# 04_LMS7002M_Misc.net
KiCad netlist of a schematic drawn in Altium Designer
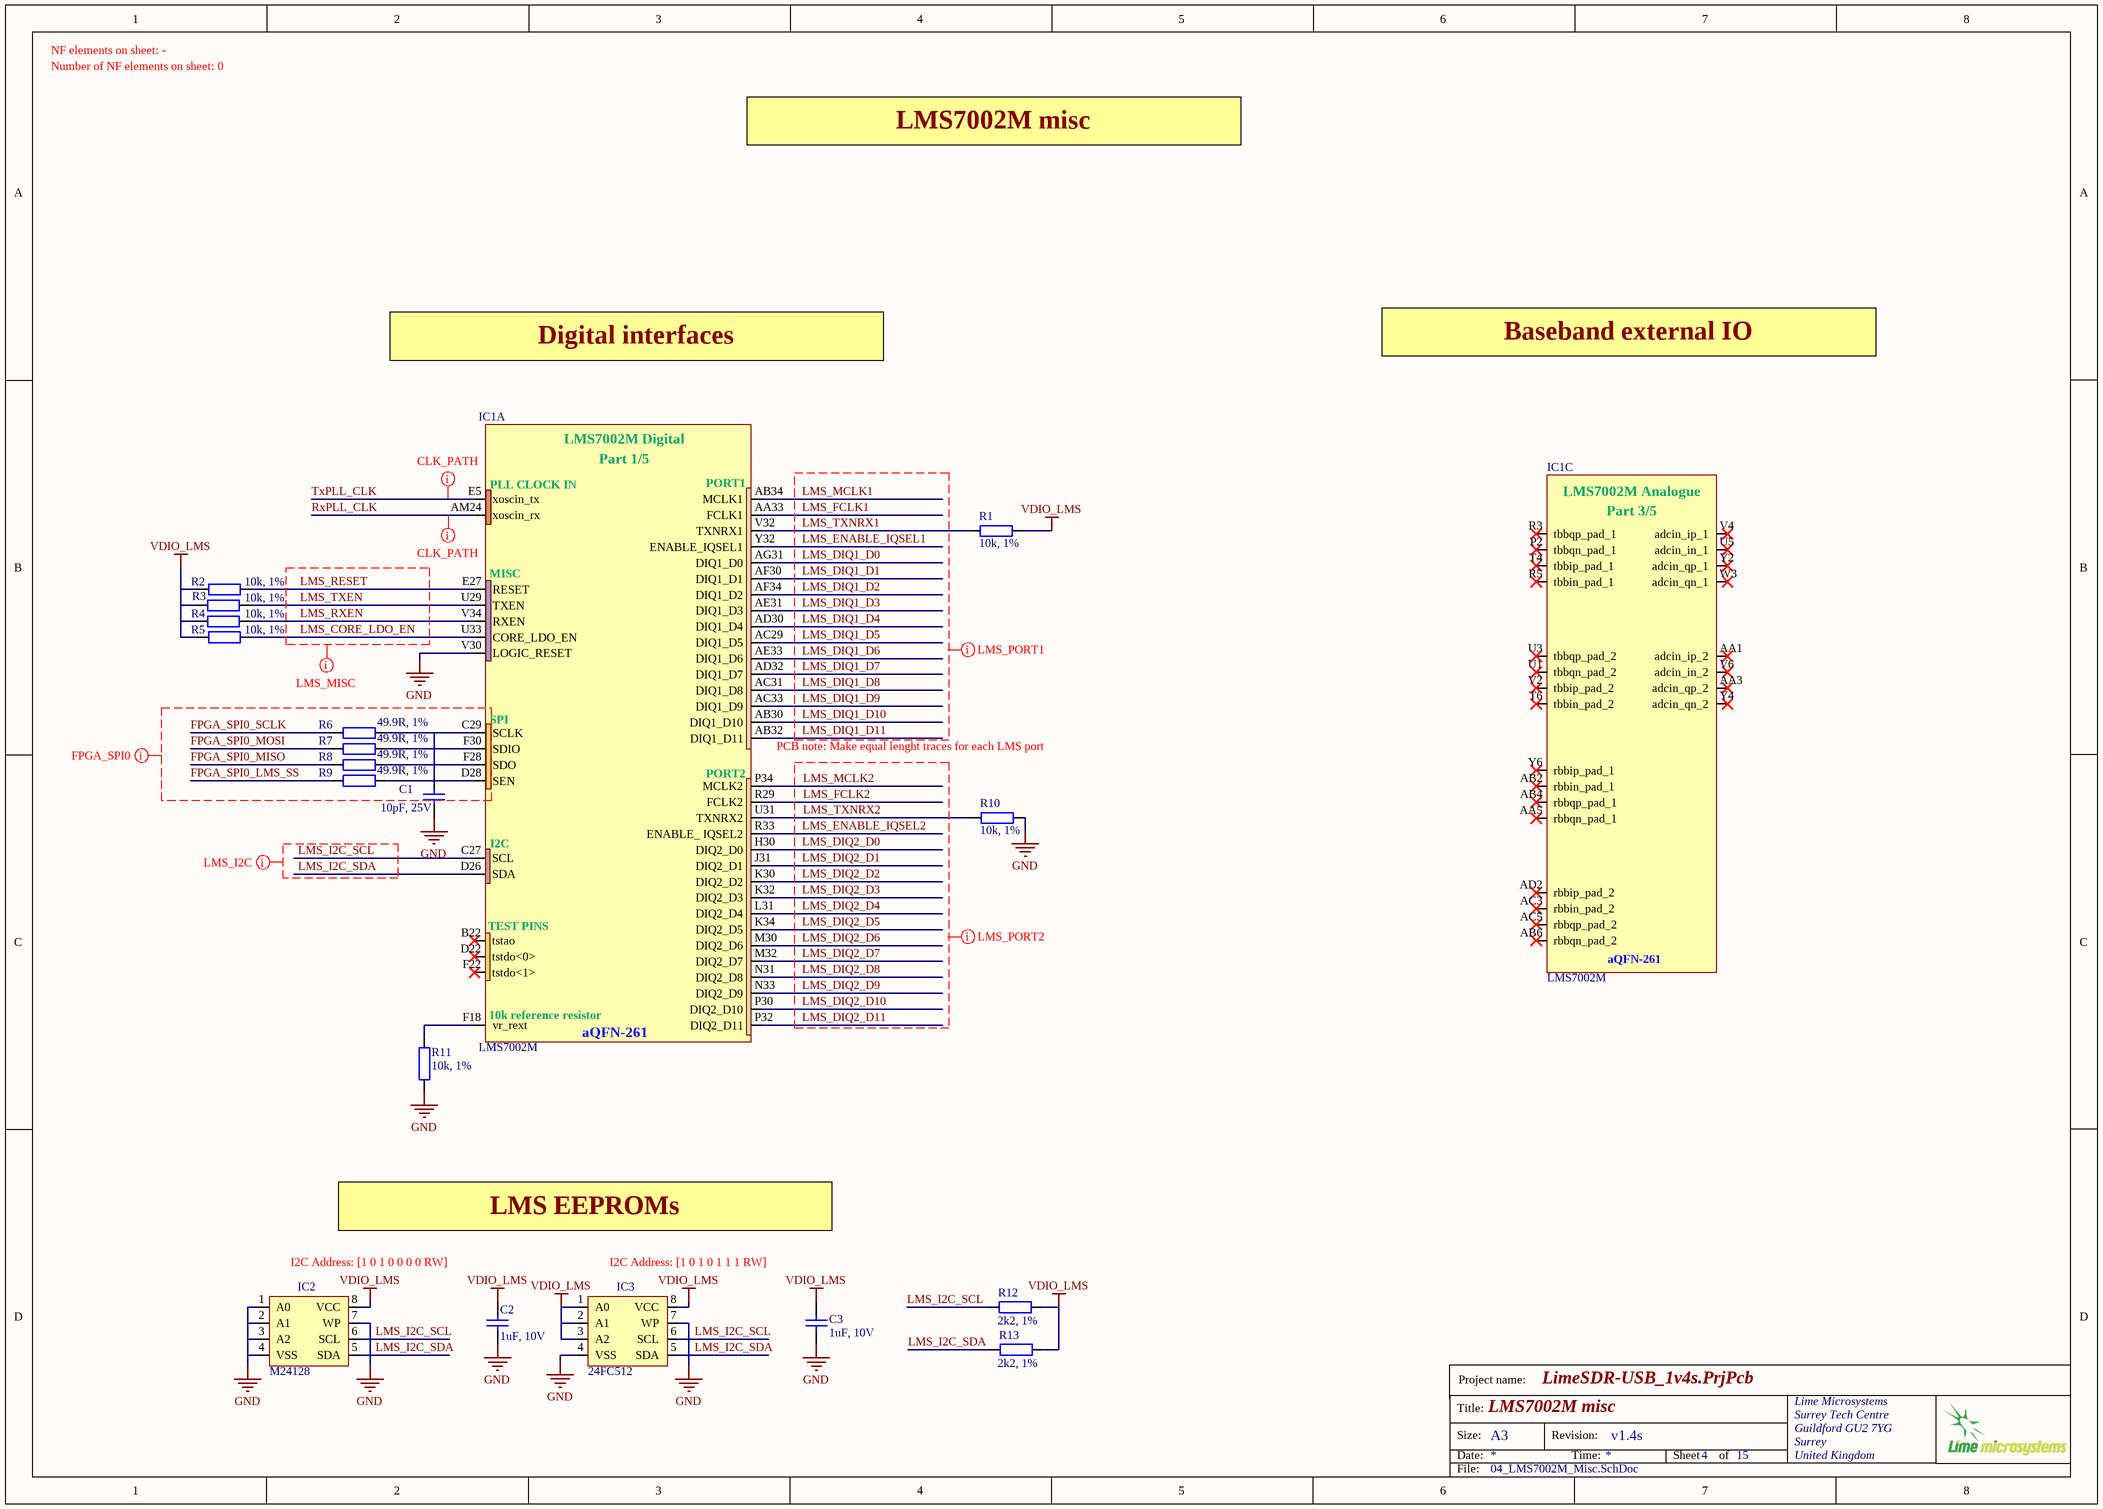
[diagram p0: 04_LMS7002M_Misc.SchDoc]

(export (version "E")
  (design (tool "Eeschema 10.0.6"))
  (components
    (comp (ref "C1")
      (value "10pF, 25V")
      (footprint "CAP0402")
      (fields (field (name "MANUFACTURER") "AVX"))
      (libsource (lib "LimeMicroAltiumLib_schLib") (part "Cap_0402"))
    )
    (comp (ref "C2")
      (value "1uF, 10V")
      (footprint "CAP0402")
      (fields (field (name "MANUFACTURER") "TDK"))
      (libsource (lib "LimeMicroAltiumLib_schLib") (part "Cap_0402"))
    )
    (comp (ref "C3")
      (value "1uF, 10V")
      (footprint "CAP0402")
      (fields (field (name "MANUFACTURER") "TDK"))
      (libsource (lib "LimeMicroAltiumLib_schLib") (part "Cap_0402"))
    )
    (comp (ref "IC1")
      (value "LMS7002M")
      (footprint "LMS7002M_v3")
      (fields (field (name "MANUFACTURER") "Lime Microsystems"))
      (libsource (lib "LimeMicroAltiumLib_schLib") (part "LMS7002M"))
    )
    (comp (ref "IC2")
      (value "M24128")
      (footprint "24FC512")
      (fields (field (name "MANUFACTURER") "STMicroelectronics"))
      (libsource (lib "LimeMicroAltiumLib_schLib") (part "24FC64F"))
    )
    (comp (ref "IC3")
      (value "24FC512")
      (footprint "24FC512")
      (fields (field (name "MANUFACTURER") "Microchip Technology"))
      (libsource (lib "LimeMicroAltiumLib_schLib") (part "24FC512"))
    )
    (comp (ref "R1")
      (value "10k, 1%")
      (footprint "RES0402")
      (fields (field (name "MANUFACTURER") "Yageo") (field (name "TOLERANCE") "±1%"))
      (libsource (lib "LimeMicroAltiumLib_schLib") (part "Res_0402"))
    )
    (comp (ref "R2")
      (value "10k, 1%")
      (footprint "RES0402")
      (fields (field (name "MANUFACTURER") "Yageo") (field (name "TOLERANCE") "±1%"))
      (libsource (lib "LimeMicroAltiumLib_schLib") (part "Res_0402"))
    )
    (comp (ref "R3")
      (value "10k, 1%")
      (footprint "RES0402")
      (fields (field (name "MANUFACTURER") "Yageo") (field (name "TOLERANCE") "±1%"))
      (libsource (lib "LimeMicroAltiumLib_schLib") (part "Res_0402"))
    )
    (comp (ref "R4")
      (value "10k, 1%")
      (footprint "RES0402")
      (fields (field (name "MANUFACTURER") "Yageo") (field (name "TOLERANCE") "±1%"))
      (libsource (lib "LimeMicroAltiumLib_schLib") (part "Res_0402"))
    )
    (comp (ref "R5")
      (value "10k, 1%")
      (footprint "RES0402")
      (fields (field (name "MANUFACTURER") "Yageo") (field (name "TOLERANCE") "±1%"))
      (libsource (lib "LimeMicroAltiumLib_schLib") (part "Res_0402"))
    )
    (comp (ref "R6")
      (value "49.9R, 1%")
      (footprint "RES0402")
      (fields
        (field (name "TOLERANCE") "±1%")
        (field (name "MANUFACTURER") "Samsung Electro-Mechanics America, Inc.")
        (field (name "MANUFACTURER PART NUMBER") "RC1005F49R9CS")
      )
      (libsource (lib "LimeMicroAltiumLib_schLib") (part "Res_0402"))
    )
    (comp (ref "R7")
      (value "49.9R, 1%")
      (footprint "RES0402")
      (fields
        (field (name "TOLERANCE") "±1%")
        (field (name "MANUFACTURER") "Samsung Electro-Mechanics America, Inc.")
        (field (name "MANUFACTURER PART NUMBER") "RC1005F49R9CS")
      )
      (libsource (lib "LimeMicroAltiumLib_schLib") (part "Res_0402"))
    )
    (comp (ref "R8")
      (value "49.9R, 1%")
      (footprint "RES0402")
      (fields
        (field (name "TOLERANCE") "±1%")
        (field (name "MANUFACTURER") "Samsung Electro-Mechanics America, Inc.")
        (field (name "MANUFACTURER PART NUMBER") "RC1005F49R9CS")
      )
      (libsource (lib "LimeMicroAltiumLib_schLib") (part "Res_0402"))
    )
    (comp (ref "R9")
      (value "49.9R, 1%")
      (footprint "RES0402")
      (fields
        (field (name "TOLERANCE") "±1%")
        (field (name "MANUFACTURER") "Samsung Electro-Mechanics America, Inc.")
        (field (name "MANUFACTURER PART NUMBER") "RC1005F49R9CS")
      )
      (libsource (lib "LimeMicroAltiumLib_schLib") (part "Res_0402"))
    )
    (comp (ref "R10")
      (value "10k, 1%")
      (footprint "RES0402")
      (fields (field (name "MANUFACTURER") "Yageo") (field (name "TOLERANCE") "±1%"))
      (libsource (lib "LimeMicroAltiumLib_schLib") (part "Res_0402"))
    )
    (comp (ref "R11")
      (value "10k, 1%")
      (footprint "RES0402")
      (fields (field (name "MANUFACTURER") "Yageo") (field (name "TOLERANCE") "±1%"))
      (libsource (lib "LimeMicroAltiumLib_schLib") (part "Res_0402"))
    )
    (comp (ref "R12")
      (value "2k2, 1%")
      (footprint "RES0402")
      (fields (field (name "MANUFACTURER") "Stackpole Electronics Inc") (field (name "TOLERANCE") "±1%"))
      (libsource (lib "LimeMicroAltiumLib_schLib") (part "Res_0402"))
    )
    (comp (ref "R13")
      (value "2k2, 1%")
      (footprint "RES0402")
      (fields (field (name "MANUFACTURER") "Stackpole Electronics Inc") (field (name "TOLERANCE") "±1%"))
      (libsource (lib "LimeMicroAltiumLib_schLib") (part "Res_0402"))
    )
  )
  (nets
    (net (code "1") (name "/FPGA_SPI0_LMS_SS") (class "Default")
      (node (ref "R9") (pin "2") (pinfunction "2_2") (pintype "passive"))
    )
    (net (code "2") (name "/FPGA_SPI0_MISO") (class "Default")
      (node (ref "R8") (pin "2") (pinfunction "2_2") (pintype "passive"))
    )
    (net (code "3") (name "/FPGA_SPI0_MOSI") (class "Default")
      (node (ref "R7") (pin "2") (pinfunction "2_2") (pintype "passive"))
    )
    (net (code "4") (name "/FPGA_SPI0_SCLK") (class "Default")
      (node (ref "R6") (pin "2") (pinfunction "2_2") (pintype "passive"))
    )
    (net (code "5") (name "/LMS_CORE_LDO_EN") (class "Default")
      (node (ref "IC1") (pin "U33") (pinfunction "CORE_LDO_EN_U33") (pintype "passive"))
      (node (ref "R5") (pin "1") (pinfunction "1_1") (pintype "passive"))
    )
    (net (code "6") (name "/LMS_DIQ1_D0") (class "Default")
      (node (ref "IC1") (pin "AG31") (pinfunction "DIQ1_D0_AG31") (pintype "passive"))
    )
    (net (code "7") (name "/LMS_DIQ1_D1") (class "Default")
      (node (ref "IC1") (pin "AF30") (pinfunction "DIQ1_D1_AF30") (pintype "passive"))
    )
    (net (code "8") (name "/LMS_DIQ1_D2") (class "Default")
      (node (ref "IC1") (pin "AF34") (pinfunction "DIQ1_D2_AF34") (pintype "passive"))
    )
    (net (code "9") (name "/LMS_DIQ1_D3") (class "Default")
      (node (ref "IC1") (pin "AE31") (pinfunction "DIQ1_D3_AE31") (pintype "passive"))
    )
    (net (code "10") (name "/LMS_DIQ1_D4") (class "Default")
      (node (ref "IC1") (pin "AD30") (pinfunction "DIQ1_D4_AD30") (pintype "passive"))
    )
    (net (code "11") (name "/LMS_DIQ1_D5") (class "Default")
      (node (ref "IC1") (pin "AC29") (pinfunction "DIQ1_D5_AC29") (pintype "passive"))
    )
    (net (code "12") (name "/LMS_DIQ1_D6") (class "Default")
      (node (ref "IC1") (pin "AE33") (pinfunction "DIQ1_D6_AE33") (pintype "passive"))
    )
    (net (code "13") (name "/LMS_DIQ1_D7") (class "Default")
      (node (ref "IC1") (pin "AD32") (pinfunction "DIQ1_D7_AD32") (pintype "passive"))
    )
    (net (code "14") (name "/LMS_DIQ1_D8") (class "Default")
      (node (ref "IC1") (pin "AC31") (pinfunction "DIQ1_D8_AC31") (pintype "passive"))
    )
    (net (code "15") (name "/LMS_DIQ1_D9") (class "Default")
      (node (ref "IC1") (pin "AC33") (pinfunction "DIQ1_D9_AC33") (pintype "passive"))
    )
    (net (code "16") (name "/LMS_DIQ1_D10") (class "Default")
      (node (ref "IC1") (pin "AB30") (pinfunction "DIQ1_D10_AB30") (pintype "passive"))
    )
    (net (code "17") (name "/LMS_DIQ1_D11") (class "Default")
      (node (ref "IC1") (pin "AB32") (pinfunction "DIQ1_D11_AB32") (pintype "passive"))
    )
    (net (code "18") (name "/LMS_DIQ2_D0") (class "Default")
      (node (ref "IC1") (pin "H30") (pinfunction "DIQ2_D0_H30") (pintype "passive"))
    )
    (net (code "19") (name "/LMS_DIQ2_D1") (class "Default")
      (node (ref "IC1") (pin "J31") (pinfunction "DIQ2_D1_J31") (pintype "passive"))
    )
    (net (code "20") (name "/LMS_DIQ2_D2") (class "Default")
      (node (ref "IC1") (pin "K30") (pinfunction "DIQ2_D2_K30") (pintype "passive"))
    )
    (net (code "21") (name "/LMS_DIQ2_D3") (class "Default")
      (node (ref "IC1") (pin "K32") (pinfunction "DIQ2_D3_K32") (pintype "passive"))
    )
    (net (code "22") (name "/LMS_DIQ2_D4") (class "Default")
      (node (ref "IC1") (pin "L31") (pinfunction "DIQ2_D4_L31") (pintype "passive"))
    )
    (net (code "23") (name "/LMS_DIQ2_D5") (class "Default")
      (node (ref "IC1") (pin "K34") (pinfunction "DIQ2_D5_K34") (pintype "passive"))
    )
    (net (code "24") (name "/LMS_DIQ2_D6") (class "Default")
      (node (ref "IC1") (pin "M30") (pinfunction "DIQ2_D6_M30") (pintype "passive"))
    )
    (net (code "25") (name "/LMS_DIQ2_D7") (class "Default")
      (node (ref "IC1") (pin "M32") (pinfunction "DIQ2_D7_M32") (pintype "passive"))
    )
    (net (code "26") (name "/LMS_DIQ2_D8") (class "Default")
      (node (ref "IC1") (pin "N31") (pinfunction "DIQ2_D8_N31") (pintype "passive"))
    )
    (net (code "27") (name "/LMS_DIQ2_D9") (class "Default")
      (node (ref "IC1") (pin "N33") (pinfunction "DIQ2_D9_N33") (pintype "passive"))
    )
    (net (code "28") (name "/LMS_DIQ2_D10") (class "Default")
      (node (ref "IC1") (pin "P30") (pinfunction "DIQ2_D10_P30") (pintype "passive"))
    )
    (net (code "29") (name "/LMS_DIQ2_D11") (class "Default")
      (node (ref "IC1") (pin "P32") (pinfunction "DIQ2_D11_P32") (pintype "passive"))
    )
    (net (code "30") (name "/LMS_ENABLE_IQSEL1") (class "Default")
      (node (ref "IC1") (pin "Y32") (pinfunction "ENABLE_IQSEL1_Y32") (pintype "passive"))
    )
    (net (code "31") (name "/LMS_ENABLE_IQSEL2") (class "Default")
      (node (ref "IC1") (pin "R33") (pinfunction "ENABLE__IQSEL2_R33") (pintype "passive"))
    )
    (net (code "32") (name "/LMS_FCLK1") (class "Default")
      (node (ref "IC1") (pin "AA33") (pinfunction "FCLK1_AA33") (pintype "passive"))
    )
    (net (code "33") (name "/LMS_FCLK2") (class "Default")
      (node (ref "IC1") (pin "R29") (pinfunction "FCLK2_R29") (pintype "passive"))
    )
    (net (code "34") (name "/LMS_I2C_SCL") (class "Default")
      (node (ref "IC1") (pin "C27") (pinfunction "SCL_C27") (pintype "passive"))
      (node (ref "IC2") (pin "6") (pinfunction "SCL_6") (pintype "passive"))
      (node (ref "IC3") (pin "6") (pinfunction "SCL_6") (pintype "passive"))
      (node (ref "R12") (pin "2") (pinfunction "2_2") (pintype "passive"))
    )
    (net (code "35") (name "/LMS_I2C_SDA") (class "Default")
      (node (ref "IC1") (pin "D26") (pinfunction "SDA_D26") (pintype "passive"))
      (node (ref "IC2") (pin "5") (pinfunction "SDA_5") (pintype "passive"))
      (node (ref "IC3") (pin "5") (pinfunction "SDA_5") (pintype "passive"))
      (node (ref "R13") (pin "2") (pinfunction "2_2") (pintype "passive"))
    )
    (net (code "36") (name "/LMS_MCLK1") (class "Default")
      (node (ref "IC1") (pin "AB34") (pinfunction "MCLK1_AB34") (pintype "passive"))
    )
    (net (code "37") (name "/LMS_MCLK2") (class "Default")
      (node (ref "IC1") (pin "P34") (pinfunction "MCLK2_P34") (pintype "passive"))
    )
    (net (code "38") (name "/LMS_RESET") (class "Default")
      (node (ref "IC1") (pin "E27") (pinfunction "RESET_E27") (pintype "passive"))
      (node (ref "R2") (pin "1") (pinfunction "1_1") (pintype "passive"))
    )
    (net (code "39") (name "/LMS_RXEN") (class "Default")
      (node (ref "IC1") (pin "V34") (pinfunction "RXEN_V34") (pintype "passive"))
      (node (ref "R4") (pin "2") (pinfunction "2_2") (pintype "passive"))
    )
    (net (code "40") (name "/LMS_TXEN") (class "Default")
      (node (ref "IC1") (pin "U29") (pinfunction "TXEN_U29") (pintype "passive"))
      (node (ref "R3") (pin "2") (pinfunction "2_2") (pintype "passive"))
    )
    (net (code "41") (name "/LMS_TXNRX1") (class "Default")
      (node (ref "IC1") (pin "V32") (pinfunction "TXNRX1_V32") (pintype "passive"))
      (node (ref "R1") (pin "1") (pinfunction "1_1") (pintype "passive"))
    )
    (net (code "42") (name "/LMS_TXNRX2") (class "Default")
      (node (ref "IC1") (pin "U31") (pinfunction "TXNRX2_U31") (pintype "passive"))
      (node (ref "R10") (pin "2") (pinfunction "2_2") (pintype "passive"))
    )
    (net (code "43") (name "/RxPLL_CLK") (class "Default")
      (node (ref "IC1") (pin "AM24") (pinfunction "xoscin_rx_AM24") (pintype "passive"))
    )
    (net (code "44") (name "/TxPLL_CLK") (class "Default")
      (node (ref "IC1") (pin "E5") (pinfunction "xoscin_tx_E5") (pintype "passive"))
    )
    (net (code "45") (name "GND") (class "Default")
      (node (ref "C1") (pin "2") (pinfunction "2_2") (pintype "passive"))
      (node (ref "C2") (pin "2") (pinfunction "2_2") (pintype "passive"))
      (node (ref "C3") (pin "1") (pinfunction "1_1") (pintype "passive"))
      (node (ref "IC1") (pin "V30") (pinfunction "LOGIC_RESET_V30") (pintype "passive"))
      (node (ref "IC2") (pin "1") (pinfunction "A0_1") (pintype "passive"))
      (node (ref "IC2") (pin "2") (pinfunction "A1_2") (pintype "passive"))
      (node (ref "IC2") (pin "3") (pinfunction "A2_3") (pintype "passive"))
      (node (ref "IC2") (pin "4") (pinfunction "VSS_4") (pintype "passive"))
      (node (ref "IC2") (pin "7") (pinfunction "WP_7") (pintype "passive"))
      (node (ref "IC3") (pin "4") (pinfunction "VSS_4") (pintype "passive"))
      (node (ref "IC3") (pin "7") (pinfunction "WP_7") (pintype "passive"))
      (node (ref "R10") (pin "1") (pinfunction "1_1") (pintype "passive"))
      (node (ref "R11") (pin "2") (pinfunction "2_2") (pintype "passive"))
    )
    (net (code "46") (name "Net-(IC1A-SCLK)") (class "Default")
      (node (ref "C1") (pin "1") (pinfunction "1_1") (pintype "passive"))
      (node (ref "IC1") (pin "C29") (pinfunction "SCLK_C29") (pintype "passive"))
      (node (ref "R6") (pin "1") (pinfunction "1_1") (pintype "passive"))
    )
    (net (code "47") (name "Net-(IC1A-SDIO)") (class "Default")
      (node (ref "IC1") (pin "F30") (pinfunction "SDIO_F30") (pintype "passive"))
      (node (ref "R7") (pin "1") (pinfunction "1_1") (pintype "passive"))
    )
    (net (code "48") (name "Net-(IC1A-SDO)") (class "Default")
      (node (ref "IC1") (pin "F28") (pinfunction "SDO_F28") (pintype "passive"))
      (node (ref "R8") (pin "1") (pinfunction "1_1") (pintype "passive"))
    )
    (net (code "49") (name "Net-(IC1A-SEN)") (class "Default")
      (node (ref "IC1") (pin "D28") (pinfunction "SEN_D28") (pintype "passive"))
      (node (ref "R9") (pin "1") (pinfunction "1_1") (pintype "passive"))
    )
    (net (code "50") (name "Net-(IC1A-vr_rext)") (class "Default")
      (node (ref "IC1") (pin "F18") (pinfunction "vr_rext_F18") (pintype "passive"))
      (node (ref "R11") (pin "1") (pinfunction "1_1") (pintype "passive"))
    )
    (net (code "51") (name "VDIO_LMS") (class "Default")
      (node (ref "C2") (pin "1") (pinfunction "1_1") (pintype "passive"))
      (node (ref "C3") (pin "2") (pinfunction "2_2") (pintype "passive"))
      (node (ref "IC2") (pin "8") (pinfunction "VCC_8") (pintype "passive"))
      (node (ref "IC3") (pin "1") (pinfunction "A0_1") (pintype "passive"))
      (node (ref "IC3") (pin "2") (pinfunction "A1_2") (pintype "passive"))
      (node (ref "IC3") (pin "3") (pinfunction "A2_3") (pintype "passive"))
      (node (ref "IC3") (pin "8") (pinfunction "VCC_8") (pintype "passive"))
      (node (ref "R1") (pin "2") (pinfunction "2_2") (pintype "passive"))
      (node (ref "R12") (pin "1") (pinfunction "1_1") (pintype "passive"))
      (node (ref "R13") (pin "1") (pinfunction "1_1") (pintype "passive"))
      (node (ref "R2") (pin "2") (pinfunction "2_2") (pintype "passive"))
      (node (ref "R3") (pin "1") (pinfunction "1_1") (pintype "passive"))
      (node (ref "R4") (pin "1") (pinfunction "1_1") (pintype "passive"))
      (node (ref "R5") (pin "2") (pinfunction "2_2") (pintype "passive"))
    )
    (net (code "52") (name "unconnected-(IC1A-tstao-PadB22)") (class "Default")
      (node (ref "IC1") (pin "B22") (pinfunction "tstao_B22") (pintype "passive+no_connect"))
    )
    (net (code "53") (name "unconnected-(IC1A-tstdo<0>-PadD22)") (class "Default")
      (node (ref "IC1") (pin "D22") (pinfunction "tstdo<0>_D22") (pintype "passive+no_connect"))
    )
    (net (code "54") (name "unconnected-(IC1A-tstdo<1>-PadF22)") (class "Default")
      (node (ref "IC1") (pin "F22") (pinfunction "tstdo<1>_F22") (pintype "passive+no_connect"))
    )
    (net (code "55") (name "unconnected-(IC1C-adcin_in_1-PadU5)") (class "Default")
      (node (ref "IC1") (pin "U5") (pinfunction "adcin_in_1_U5") (pintype "passive+no_connect"))
    )
    (net (code "56") (name "unconnected-(IC1C-adcin_in_2-PadV6)") (class "Default")
      (node (ref "IC1") (pin "V6") (pinfunction "adcin_in_2_V6") (pintype "passive+no_connect"))
    )
    (net (code "57") (name "unconnected-(IC1C-adcin_ip_1-PadV4)") (class "Default")
      (node (ref "IC1") (pin "V4") (pinfunction "adcin_ip_1_V4") (pintype "passive+no_connect"))
    )
    (net (code "58") (name "unconnected-(IC1C-adcin_ip_2-PadAA1)") (class "Default")
      (node (ref "IC1") (pin "AA1") (pinfunction "adcin_ip_2_AA1") (pintype "passive+no_connect"))
    )
    (net (code "59") (name "unconnected-(IC1C-adcin_qn_1-PadW3)") (class "Default")
      (node (ref "IC1") (pin "W3") (pinfunction "adcin_qn_1_W3") (pintype "passive+no_connect"))
    )
    (net (code "60") (name "unconnected-(IC1C-adcin_qn_2-PadY4)") (class "Default")
      (node (ref "IC1") (pin "Y4") (pinfunction "adcin_qn_2_Y4") (pintype "passive+no_connect"))
    )
    (net (code "61") (name "unconnected-(IC1C-adcin_qp_1-PadY2)") (class "Default")
      (node (ref "IC1") (pin "Y2") (pinfunction "adcin_qp_1_Y2") (pintype "passive+no_connect"))
    )
    (net (code "62") (name "unconnected-(IC1C-adcin_qp_2-PadAA3)") (class "Default")
      (node (ref "IC1") (pin "AA3") (pinfunction "adcin_qp_2_AA3") (pintype "passive+no_connect"))
    )
    (net (code "63") (name "unconnected-(IC1C-rbbin_pad_1-PadAB2)") (class "Default")
      (node (ref "IC1") (pin "AB2") (pinfunction "rbbin_pad_1_AB2") (pintype "passive+no_connect"))
    )
    (net (code "64") (name "unconnected-(IC1C-rbbin_pad_2-PadAC3)") (class "Default")
      (node (ref "IC1") (pin "AC3") (pinfunction "rbbin_pad_2_AC3") (pintype "passive+no_connect"))
    )
    (net (code "65") (name "unconnected-(IC1C-rbbip_pad_1-PadY6)") (class "Default")
      (node (ref "IC1") (pin "Y6") (pinfunction "rbbip_pad_1_Y6") (pintype "passive+no_connect"))
    )
    (net (code "66") (name "unconnected-(IC1C-rbbip_pad_2-PadAD2)") (class "Default")
      (node (ref "IC1") (pin "AD2") (pinfunction "rbbip_pad_2_AD2") (pintype "passive+no_connect"))
    )
    (net (code "67") (name "unconnected-(IC1C-rbbqn_pad_1-PadAA5)") (class "Default")
      (node (ref "IC1") (pin "AA5") (pinfunction "rbbqn_pad_1_AA5") (pintype "passive+no_connect"))
    )
    (net (code "68") (name "unconnected-(IC1C-rbbqn_pad_2-PadAB6)") (class "Default")
      (node (ref "IC1") (pin "AB6") (pinfunction "rbbqn_pad_2_AB6") (pintype "passive+no_connect"))
    )
    (net (code "69") (name "unconnected-(IC1C-rbbqp_pad_1-PadAB4)") (class "Default")
      (node (ref "IC1") (pin "AB4") (pinfunction "rbbqp_pad_1_AB4") (pintype "passive+no_connect"))
    )
    (net (code "70") (name "unconnected-(IC1C-rbbqp_pad_2-PadAC5)") (class "Default")
      (node (ref "IC1") (pin "AC5") (pinfunction "rbbqp_pad_2_AC5") (pintype "passive+no_connect"))
    )
    (net (code "71") (name "unconnected-(IC1C-tbbin_pad_1-PadR5)") (class "Default")
      (node (ref "IC1") (pin "R5") (pinfunction "tbbin_pad_1_R5") (pintype "passive+no_connect"))
    )
    (net (code "72") (name "unconnected-(IC1C-tbbin_pad_2-PadT6)") (class "Default")
      (node (ref "IC1") (pin "T6") (pinfunction "tbbin_pad_2_T6") (pintype "passive+no_connect"))
    )
    (net (code "73") (name "unconnected-(IC1C-tbbip_pad_1-PadT4)") (class "Default")
      (node (ref "IC1") (pin "T4") (pinfunction "tbbip_pad_1_T4") (pintype "passive+no_connect"))
    )
    (net (code "74") (name "unconnected-(IC1C-tbbip_pad_2-PadV2)") (class "Default")
      (node (ref "IC1") (pin "V2") (pinfunction "tbbip_pad_2_V2") (pintype "passive+no_connect"))
    )
    (net (code "75") (name "unconnected-(IC1C-tbbqn_pad_1-PadP2)") (class "Default")
      (node (ref "IC1") (pin "P2") (pinfunction "tbbqn_pad_1_P2") (pintype "passive+no_connect"))
    )
    (net (code "76") (name "unconnected-(IC1C-tbbqn_pad_2-PadU1)") (class "Default")
      (node (ref "IC1") (pin "U1") (pinfunction "tbbqn_pad_2_U1") (pintype "passive+no_connect"))
    )
    (net (code "77") (name "unconnected-(IC1C-tbbqp_pad_1-PadR3)") (class "Default")
      (node (ref "IC1") (pin "R3") (pinfunction "tbbqp_pad_1_R3") (pintype "passive+no_connect"))
    )
    (net (code "78") (name "unconnected-(IC1C-tbbqp_pad_2-PadU3)") (class "Default")
      (node (ref "IC1") (pin "U3") (pinfunction "tbbqp_pad_2_U3") (pintype "passive+no_connect"))
    )
  )
)
